# Page1.net
KiCad netlist of a schematic drawn in Altium Designer
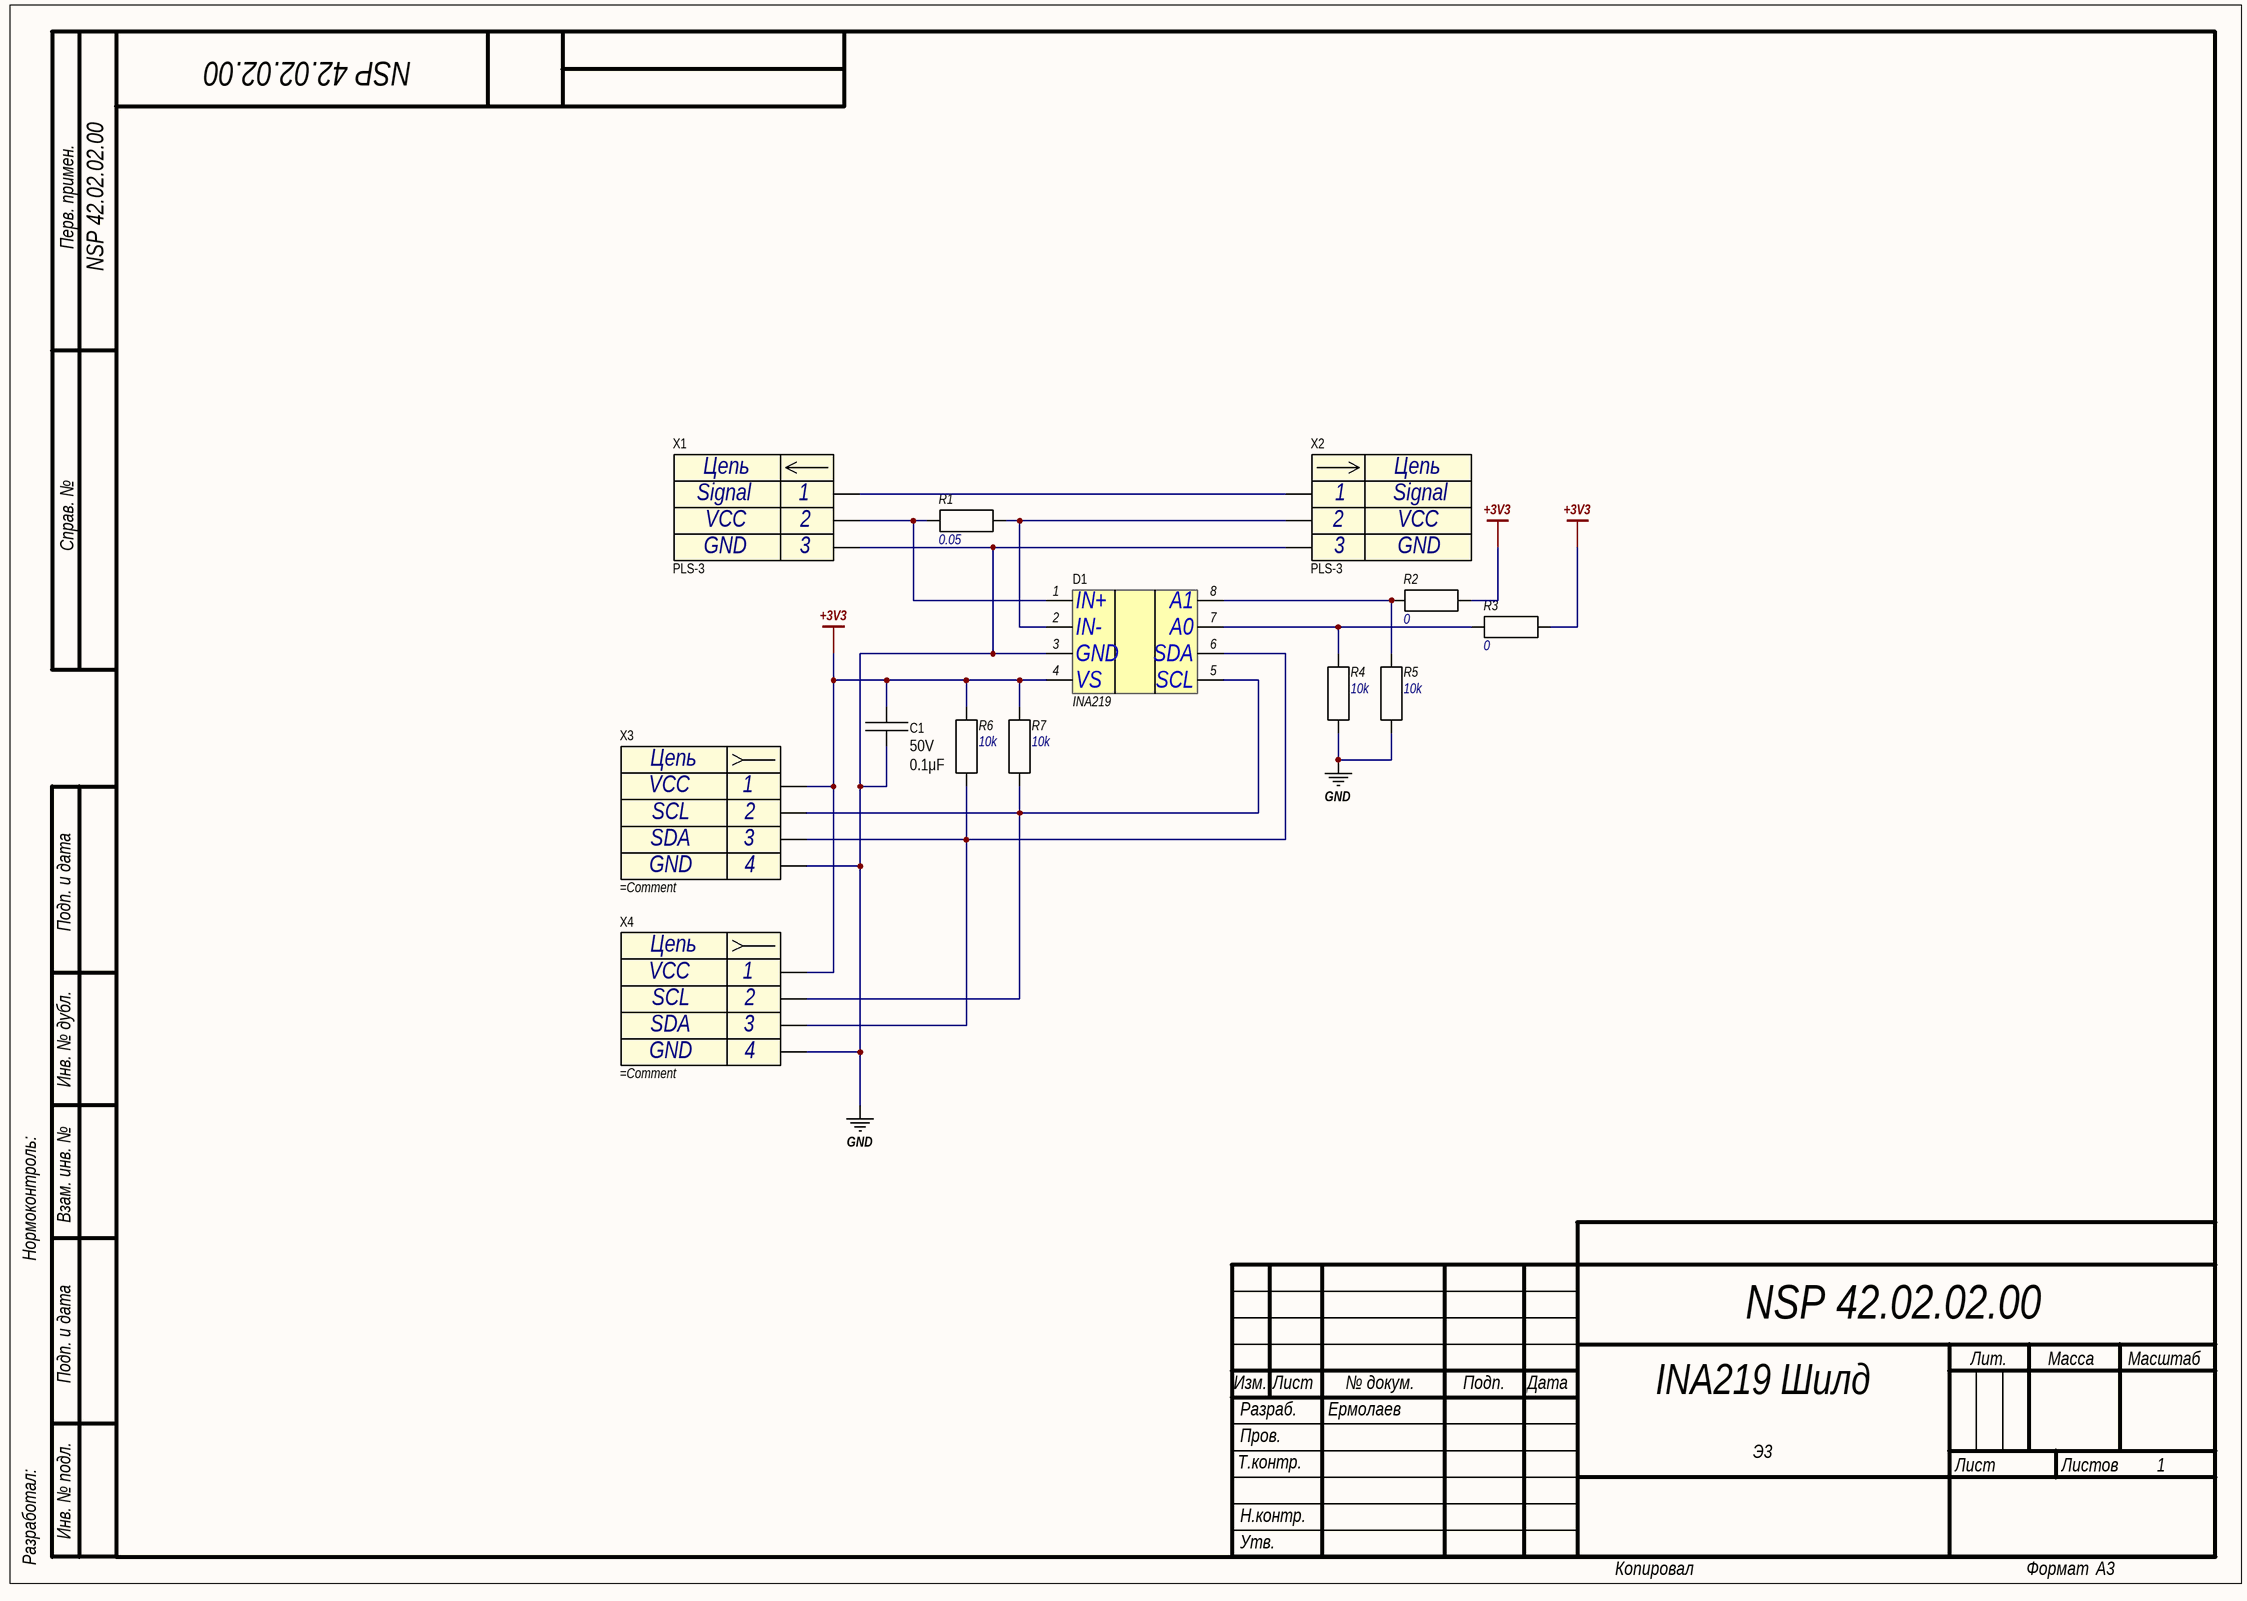
[diagram p0: Page1.SchDoc]

(export (version "E")
  (design (tool "Eeschema 10.0.6"))
  (components
    (comp (ref "C1")
      (value "0.1μF")
      (footprint "CAP: 1206")
      (fields
        (field (name "MANUFACTURER") "Yageo")
        (field (name "PARTNUMBER") "CC1206KRX7R9BB104")
        (field (name "VALUEMANUFACTURERPARTNUMBER") "Ceramic capacitor, 0.1μF, X7R, ±10%, 50V, 1206, -55...+125°C")
        (field (name "VOLTAGE") "50V")
      )
      (libsource (lib "Capacitor") (part "Ceramic_1206"))
    )
    (comp (ref "D1")
      (value "INA219")
      (footprint "SOT23-8")
      (fields (field (name "PART NUMBER") "INA219AIDCNR"))
      (libsource (lib "Oleg Lib") (part "INA219"))
    )
    (comp (ref "R1")
      (value "0.05")
      (footprint "R2010")
      (fields (field (name "PART NUMBER") "RL2010FK-070R05L"))
      (libsource (lib "Oleg Lib") (part "Резистор"))
    )
    (comp (ref "R2")
      (value "0")
      (footprint "R1206")
      (fields (field (name "PART NUMBER") "RC1206FR-070RL"))
      (libsource (lib "Oleg Lib") (part "Резистор"))
    )
    (comp (ref "R3")
      (value "0")
      (footprint "R1206")
      (fields (field (name "PART NUMBER") "RC1206FR-070RL"))
      (libsource (lib "Oleg Lib") (part "Резистор"))
    )
    (comp (ref "R4")
      (value "10k")
      (footprint "R1206")
      (fields (field (name "PART NUMBER") "RC1206FR-0710KL"))
      (libsource (lib "") (part "Резистор_1"))
    )
    (comp (ref "R5")
      (value "10k")
      (footprint "R1206")
      (fields (field (name "PART NUMBER") "RC1206FR-0710KL"))
      (libsource (lib "Oleg Lib") (part "Резистор"))
    )
    (comp (ref "R6")
      (value "10k")
      (footprint "R1206")
      (fields (field (name "PART NUMBER") "RC1206FR-0710KL"))
      (libsource (lib "Oleg Lib") (part "Резистор"))
    )
    (comp (ref "R7")
      (value "10k")
      (footprint "R1206")
      (fields (field (name "PART NUMBER") "RC1206FR-0710KL"))
      (libsource (lib "Oleg Lib") (part "Резистор"))
    )
    (comp (ref "X1") (value "PLS-3") (footprint "PLS-3") (libsource (lib "") (part "PLS-3_1")))
    (comp (ref "X2") (value "PLS-3") (footprint "PLS-3") (libsource (lib "Oleg Lib") (part "PLS-3")))
    (comp (ref "X3") (value "~") (footprint "RJ-9_4p4c") (libsource (lib "Oleg Lib") (part "rj-11")))
    (comp (ref "X4") (value "~") (footprint "RJ-9_4p4c") (libsource (lib "Oleg Lib") (part "rj-11")))
  )
  (nets
    (net (code "1") (name "+3V3") (class "Default")
      (node (ref "C1") (pin "2") (pinfunction "2_2") (pintype "power_in"))
      (node (ref "D1") (pin "4") (pinfunction "VS_4") (pintype "passive"))
      (node (ref "R2") (pin "2") (pinfunction "2_2") (pintype "passive"))
      (node (ref "R3") (pin "2") (pinfunction "2_2") (pintype "passive"))
      (node (ref "R6") (pin "2") (pinfunction "2_2") (pintype "passive"))
      (node (ref "R7") (pin "2") (pinfunction "2_2") (pintype "passive"))
      (node (ref "X3") (pin "1") (pinfunction "1_1") (pintype "passive"))
      (node (ref "X4") (pin "1") (pinfunction "1_1") (pintype "passive"))
    )
    (net (code "2") (name "GND") (class "Default")
      (node (ref "C1") (pin "1") (pinfunction "1_1") (pintype "power_in"))
      (node (ref "D1") (pin "3") (pinfunction "GND_3") (pintype "passive"))
      (node (ref "R4") (pin "1") (pinfunction "1_1") (pintype "passive"))
      (node (ref "R5") (pin "1") (pinfunction "1_1") (pintype "passive"))
      (node (ref "X1") (pin "3") (pinfunction "3_3") (pintype "passive"))
      (node (ref "X2") (pin "3") (pinfunction "3_3") (pintype "passive"))
      (node (ref "X3") (pin "4") (pinfunction "4_4") (pintype "passive"))
      (node (ref "X4") (pin "4") (pinfunction "4_4") (pintype "passive"))
    )
    (net (code "3") (name "Net-(D1-A0)") (class "Default")
      (node (ref "D1") (pin "7") (pinfunction "A0_7") (pintype "passive"))
      (node (ref "R3") (pin "1") (pinfunction "1_1") (pintype "passive"))
      (node (ref "R4") (pin "2") (pinfunction "2_2") (pintype "passive"))
    )
    (net (code "4") (name "Net-(D1-A1)") (class "Default")
      (node (ref "D1") (pin "8") (pinfunction "A1_8") (pintype "passive"))
      (node (ref "R2") (pin "1") (pinfunction "1_1") (pintype "passive"))
      (node (ref "R5") (pin "2") (pinfunction "2_2") (pintype "passive"))
    )
    (net (code "5") (name "Net-(D1-IN+)") (class "Default")
      (node (ref "D1") (pin "1") (pinfunction "IN+_1") (pintype "passive"))
      (node (ref "R1") (pin "1") (pinfunction "1_1") (pintype "passive"))
      (node (ref "X1") (pin "2") (pinfunction "2_2") (pintype "passive"))
    )
    (net (code "6") (name "Net-(D1-IN-)") (class "Default")
      (node (ref "D1") (pin "2") (pinfunction "IN-_2") (pintype "passive"))
      (node (ref "R1") (pin "2") (pinfunction "2_2") (pintype "passive"))
      (node (ref "X2") (pin "2") (pinfunction "2_2") (pintype "passive"))
    )
    (net (code "7") (name "Net-(D1-SCL)") (class "Default")
      (node (ref "D1") (pin "5") (pinfunction "SCL_5") (pintype "passive"))
      (node (ref "R7") (pin "1") (pinfunction "1_1") (pintype "passive"))
      (node (ref "X3") (pin "2") (pinfunction "2_2") (pintype "passive"))
      (node (ref "X4") (pin "2") (pinfunction "2_2") (pintype "passive"))
    )
    (net (code "8") (name "Net-(D1-SDA)") (class "Default")
      (node (ref "D1") (pin "6") (pinfunction "SDA_6") (pintype "passive"))
      (node (ref "R6") (pin "1") (pinfunction "1_1") (pintype "passive"))
      (node (ref "X3") (pin "3") (pinfunction "3_3") (pintype "passive"))
      (node (ref "X4") (pin "3") (pinfunction "3_3") (pintype "passive"))
    )
    (net (code "9") (name "Net-(X1-Pad1)") (class "Default")
      (node (ref "X1") (pin "1") (pinfunction "1_1") (pintype "passive"))
      (node (ref "X2") (pin "1") (pinfunction "1_1") (pintype "passive"))
    )
  )
)
